# MCU-connectors-schematic.net
KiCad netlist of a schematic drawn in Altium Designer
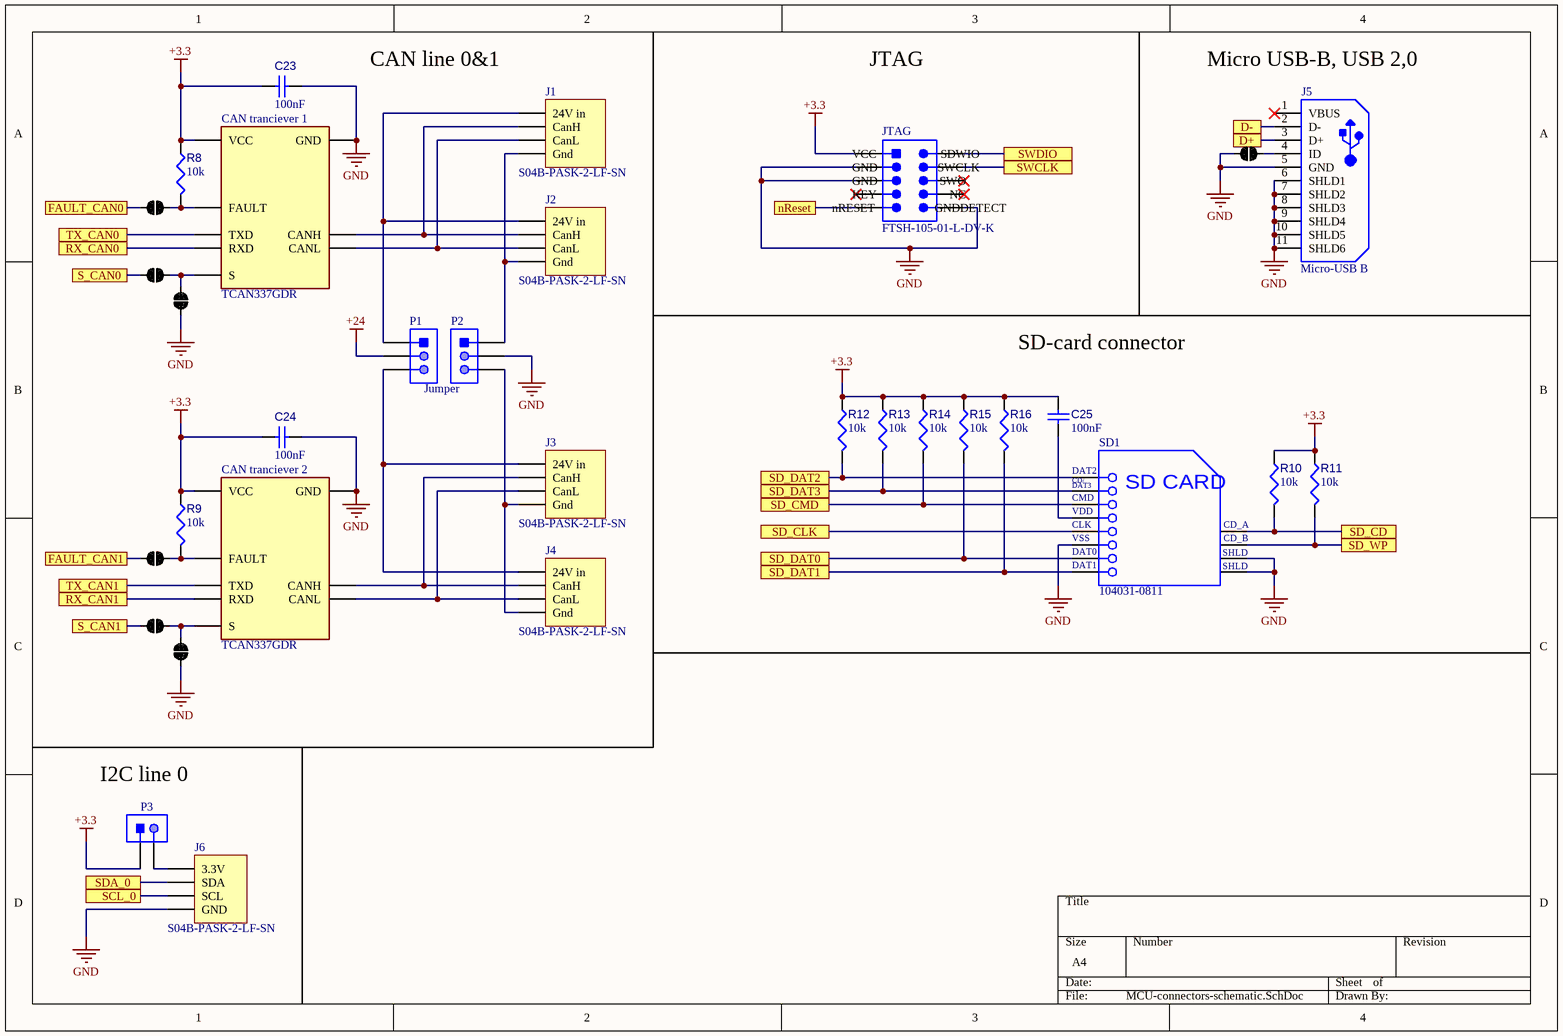
[diagram p0: MCU-connectors-schematic.SchDoc]

(export (version "E")
  (design (tool "Eeschema 10.0.6"))
  (components
    (comp (ref "C23")
      (value "100nF")
      (footprint "CAPC1608X90X40ML10T20")
      (description "Chip Capacitor, 100 nF, +/- 10%, 50 V, 0603 (1608 Metric)")
      (fields (field (name "TOLERANCE") "10%") (field (name "Comment") "Capacitor 100 nF +/-10% 50 V 0603"))
      (libsource (lib "EPFL") (part "CAP-NP-2"))
    )
    (comp (ref "C24")
      (value "100nF")
      (footprint "CAPC1608X90X40ML10T20")
      (description "Chip Capacitor, 100 nF, +/- 10%, 50 V, 0603 (1608 Metric)")
      (fields (field (name "TOLERANCE") "10%") (field (name "Comment") "Capacitor 100 nF +/-10% 50 V 0603"))
      (libsource (lib "EPFL") (part "CAP-NP-2"))
    )
    (comp (ref "C25")
      (value "100nF")
      (footprint "CAPC1608X90X40ML10T20")
      (description "Chip Capacitor, 100 nF, +/- 10%, 50 V, 0603 (1608 Metric)")
      (fields (field (name "TOLERANCE") "10%") (field (name "Comment") "Capacitor 100 nF +/-10% 50 V 0603"))
      (libsource (lib "EPFL") (part "CAP-NP-2"))
    )
    (comp (ref "CAN tranciever 1")
      (value "TCAN337GDR")
      (footprint "FP-D0008A-IPC_B")
      (description "3.3-V CAN Transceivers with CAN FD (Flexible Data Rate) 8-SOIC -40 to 125")
      (libsource (lib "EPFL") (part "a138acb6fe070981c36b7847827baee"))
    )
    (comp (ref "CAN tranciever 2")
      (value "TCAN337GDR")
      (footprint "FP-D0008A-IPC_B")
      (description "3.3-V CAN Transceivers with CAN FD (Flexible Data Rate) 8-SOIC -40 to 125")
      (libsource (lib "EPFL") (part "a138acb6fe070981c36b7847827baee"))
    )
    (comp (ref "J1")
      (value "S04B-PASK-2-LF-SN")
      (footprint "JST-B4B-PH-K-S_V")
      (libsource (lib "EPFL") (part "New symbol 1"))
    )
    (comp (ref "J2")
      (value "S04B-PASK-2-LF-SN")
      (footprint "JST-B4B-PH-K-S_V")
      (libsource (lib "EPFL") (part "New symbol 1"))
    )
    (comp (ref "J3")
      (value "S04B-PASK-2-LF-SN")
      (footprint "JST-B4B-PH-K-S_V")
      (libsource (lib "EPFL") (part "New symbol 1"))
    )
    (comp (ref "J4")
      (value "S04B-PASK-2-LF-SN")
      (footprint "JST-B4B-PH-K-S_V")
      (libsource (lib "EPFL") (part "New symbol 1"))
    )
    (comp (ref "J5")
      (value "Micro-USB B")
      (footprint "USB-MICRO-B_V")
      (fields (field (name "MANUFACTURER") "Molex"))
      (libsource (lib "Altium Content Vault") (part "USB-5-6SHLD"))
    )
    (comp (ref "J6")
      (value "S04B-PASK-2-LF-SN")
      (footprint "JST-B4B-PH-K-S_V")
      (libsource (lib "EPFL") (part "I2C connector"))
    )
    (comp (ref "JTAG")
      (value "FTSH-105-01-L-DV-K")
      (footprint "SMTC-FTSH-105-01-L-DV-K_V")
      (description "Male Header, Pitch 1.27 mm, 2 x 5 Position, Height 6.25 mm")
      (fields (field (name "MANUFACTURER") "Samtec"))
      (libsource (lib "Altium Content Vault") (part "CN-2P-M-R10"))
    )
    (comp (ref "P1")
      (value "22-28-4033")
      (footprint "MOLX-22-28-4033_V")
      (description "Male Header, Pitch 2.54 mm, 1 x 3 Position, Height 8.38 mm, Tail Length 3.18 mm, RoHS, Bulk")
      (fields (field (name "MANUFACTURER") "Molex"))
      (libsource (lib "Altium Content Vault") (part "CN-1P-M-R3"))
    )
    (comp (ref "P2")
      (value "22-28-4033")
      (footprint "MOLX-22-28-4033_V")
      (description "Male Header, Pitch 2.54 mm, 1 x 3 Position, Height 8.38 mm, Tail Length 3.18 mm, RoHS, Bulk")
      (fields (field (name "MANUFACTURER") "Molex"))
      (libsource (lib "") (part "CN-1P-M-R3_1"))
    )
    (comp (ref "P3")
      (value "61900211121")
      (footprint "61900211121")
      (description "Male Locking Header WR-WTB, THT, Vertical, pitch 2.54 mm, 1 x 2 position")
      (fields (field (name "MANUFACTURER") "Wurth Elektronik") (field (name "PUBLISHER") "WurthElektronik"))
      (libsource (lib "Altium Content Vault") (part "WE-CN-1P-M-R2"))
    )
    (comp (ref "R8")
      (value "10k")
      (footprint "RESC1608X55X25ML10T15")
      (description "Chip Resistor, 10 KOhm, +/- 1%, 01 W, -55 to 155 degC, 0603 (1608 Metric)")
      (fields (field (name "TOLERANCE") "1%") (field (name "POWER") "100mW"))
      (libsource (lib "EPFL") (part "RES-2"))
    )
    (comp (ref "R9")
      (value "10k")
      (footprint "RESC1608X55X25ML10T15")
      (description "Chip Resistor, 10 KOhm, +/- 1%, 01 W, -55 to 155 degC, 0603 (1608 Metric)")
      (fields (field (name "TOLERANCE") "1%") (field (name "POWER") "100mW"))
      (libsource (lib "EPFL") (part "RES-2"))
    )
    (comp (ref "R10")
      (value "10k")
      (footprint "RESC1608X55X25ML10T15")
      (description "Chip Resistor, 10 KOhm, +/- 1%, 01 W, -55 to 155 degC, 0603 (1608 Metric)")
      (fields (field (name "TOLERANCE") "1%") (field (name "POWER") "100mW"))
      (libsource (lib "EPFL") (part "RES-2"))
    )
    (comp (ref "R11")
      (value "10k")
      (footprint "RESC1608X55X25ML10T15")
      (description "Chip Resistor, 10 KOhm, +/- 1%, 01 W, -55 to 155 degC, 0603 (1608 Metric)")
      (fields (field (name "TOLERANCE") "1%") (field (name "POWER") "100mW"))
      (libsource (lib "EPFL") (part "RES-2"))
    )
    (comp (ref "R12")
      (value "10k")
      (footprint "RESC1608X55X25ML10T15")
      (description "Chip Resistor, 10 KOhm, +/- 1%, 01 W, -55 to 155 degC, 0603 (1608 Metric)")
      (fields (field (name "TOLERANCE") "1%") (field (name "POWER") "100mW"))
      (libsource (lib "EPFL") (part "RES-2"))
    )
    (comp (ref "R13")
      (value "10k")
      (footprint "RESC1608X55X25ML10T15")
      (description "Chip Resistor, 10 KOhm, +/- 1%, 01 W, -55 to 155 degC, 0603 (1608 Metric)")
      (fields (field (name "TOLERANCE") "1%") (field (name "POWER") "100mW"))
      (libsource (lib "EPFL") (part "RES-2"))
    )
    (comp (ref "R14")
      (value "10k")
      (footprint "RESC1608X55X25ML10T15")
      (description "Chip Resistor, 10 KOhm, +/- 1%, 01 W, -55 to 155 degC, 0603 (1608 Metric)")
      (fields (field (name "TOLERANCE") "1%") (field (name "POWER") "100mW"))
      (libsource (lib "EPFL") (part "RES-2"))
    )
    (comp (ref "R15")
      (value "10k")
      (footprint "RESC1608X55X25ML10T15")
      (description "Chip Resistor, 10 KOhm, +/- 1%, 01 W, -55 to 155 degC, 0603 (1608 Metric)")
      (fields (field (name "TOLERANCE") "1%") (field (name "POWER") "100mW"))
      (libsource (lib "EPFL") (part "RES-2"))
    )
    (comp (ref "R16")
      (value "10k")
      (footprint "RESC1608X55X25ML10T15")
      (description "Chip Resistor, 10 KOhm, +/- 1%, 01 W, -55 to 155 degC, 0603 (1608 Metric)")
      (fields (field (name "TOLERANCE") "1%") (field (name "POWER") "100mW"))
      (libsource (lib "EPFL") (part "RES-2"))
    )
    (comp (ref "SD1")
      (value "104031-0811")
      (footprint "MOLX-104031-0811_V")
      (description "Micro SD Card, RA, -25 to 85 degC, 8-Pin SMD, RoHS, Tape and Reel")
      (fields (field (name "MANUFACTURER") "Molex"))
      (libsource (lib "Altium Content Vault") (part "CN-SD-8-2SW-2S"))
    )
    (comp (ref "SJ1")
      (value "custom Solder bridge")
      (footprint "custom Solder bridge-Footprint-1")
      (description "custom solder bridge")
      (libsource (lib "EPFL") (part "Solder bridge"))
    )
    (comp (ref "SJ2")
      (value "custom Solder bridge")
      (footprint "custom Solder bridge-Footprint-1")
      (description "custom solder bridge")
      (libsource (lib "EPFL") (part "Solder bridge"))
    )
    (comp (ref "SJ3")
      (value "custom Solder bridge")
      (footprint "custom Solder bridge-Footprint-1")
      (description "custom solder bridge")
      (libsource (lib "EPFL") (part "Solder bridge"))
    )
    (comp (ref "SJ4")
      (value "custom Solder bridge")
      (footprint "custom Solder bridge-Footprint-1")
      (description "custom solder bridge")
      (libsource (lib "EPFL") (part "Solder bridge"))
    )
    (comp (ref "SJ5")
      (value "custom Solder bridge")
      (footprint "custom Solder bridge-Footprint-1")
      (description "custom solder bridge")
      (libsource (lib "EPFL") (part "Solder bridge"))
    )
    (comp (ref "SJ6")
      (value "custom Solder bridge")
      (footprint "custom Solder bridge-Footprint-1")
      (description "custom solder bridge")
      (libsource (lib "EPFL") (part "Solder bridge"))
    )
    (comp (ref "SJ7")
      (value "custom Solder bridge")
      (footprint "custom Solder bridge-Footprint-1")
      (description "custom solder bridge")
      (libsource (lib "EPFL") (part "Solder bridge"))
    )
  )
  (nets
    (net (code "1") (name "+3.3") (class "Default")
      (node (ref "C23") (pin "2") (pinfunction "2_2") (pintype "passive"))
      (node (ref "C24") (pin "2") (pinfunction "2_2") (pintype "passive"))
      (node (ref "C25") (pin "2") (pinfunction "2_2") (pintype "passive"))
      (node (ref "CAN tranciever 1") (pin "3") (pinfunction "VCC_3") (pintype "power_in"))
      (node (ref "CAN tranciever 2") (pin "3") (pinfunction "VCC_3") (pintype "power_in"))
      (node (ref "JTAG") (pin "1") (pinfunction "VCC_1") (pintype "passive"))
      (node (ref "P3") (pin "1") (pinfunction "1_1") (pintype "passive"))
      (node (ref "R10") (pin "1") (pinfunction "1_1") (pintype "passive"))
      (node (ref "R11") (pin "1") (pinfunction "1_1") (pintype "passive"))
      (node (ref "R12") (pin "1") (pinfunction "1_1") (pintype "passive"))
      (node (ref "R13") (pin "1") (pinfunction "1_1") (pintype "passive"))
      (node (ref "R14") (pin "1") (pinfunction "1_1") (pintype "passive"))
      (node (ref "R15") (pin "1") (pinfunction "1_1") (pintype "passive"))
      (node (ref "R16") (pin "1") (pinfunction "1_1") (pintype "passive"))
      (node (ref "R8") (pin "1") (pinfunction "1_1") (pintype "passive"))
      (node (ref "R9") (pin "1") (pinfunction "1_1") (pintype "passive"))
    )
    (net (code "2") (name "+24") (class "Default")
      (node (ref "P1") (pin "2") (pinfunction "2_2") (pintype "passive"))
    )
    (net (code "3") (name "/D+") (class "Default")
      (node (ref "J5") (pin "3") (pinfunction "D+_3") (pintype "passive"))
    )
    (net (code "4") (name "/D-") (class "Default")
      (node (ref "J5") (pin "2") (pinfunction "D-_2") (pintype "passive"))
    )
    (net (code "5") (name "/FAULT_CAN0") (class "Default")
      (node (ref "SJ6") (pin "1") (pinfunction "1_1") (pintype "passive"))
    )
    (net (code "6") (name "/FAULT_CAN1") (class "Default")
      (node (ref "SJ3") (pin "1") (pinfunction "1_1") (pintype "passive"))
    )
    (net (code "7") (name "/RX_CAN0") (class "Default")
      (node (ref "CAN tranciever 1") (pin "4") (pinfunction "RXD_4") (pintype "passive"))
    )
    (net (code "8") (name "/RX_CAN1") (class "Default")
      (node (ref "CAN tranciever 2") (pin "4") (pinfunction "RXD_4") (pintype "passive"))
    )
    (net (code "9") (name "/SCL_0") (class "Default")
      (node (ref "J6") (pin "3") (pinfunction "SCL_3") (pintype "passive"))
    )
    (net (code "10") (name "/SDA_0") (class "Default")
      (node (ref "J6") (pin "2") (pinfunction "SDA_2") (pintype "passive"))
    )
    (net (code "11") (name "/SD_CD") (class "Default")
      (node (ref "R10") (pin "2") (pinfunction "2_2") (pintype "passive"))
      (node (ref "SD1") (pin "9") (pinfunction "CD_A_9") (pintype "passive"))
    )
    (net (code "12") (name "/SD_CLK") (class "Default")
      (node (ref "SD1") (pin "5") (pinfunction "CLK_5") (pintype "passive"))
    )
    (net (code "13") (name "/SD_CMD") (class "Default")
      (node (ref "R14") (pin "2") (pinfunction "2_2") (pintype "passive"))
      (node (ref "SD1") (pin "3") (pinfunction "VSS1_3") (pintype "passive"))
    )
    (net (code "14") (name "/SD_DAT0") (class "Default")
      (node (ref "R15") (pin "2") (pinfunction "2_2") (pintype "passive"))
      (node (ref "SD1") (pin "7") (pinfunction "DAT0_7") (pintype "passive"))
    )
    (net (code "15") (name "/SD_DAT1") (class "Default")
      (node (ref "R16") (pin "2") (pinfunction "2_2") (pintype "passive"))
      (node (ref "SD1") (pin "8") (pinfunction "DAT1_8") (pintype "passive"))
    )
    (net (code "16") (name "/SD_DAT2") (class "Default")
      (node (ref "R12") (pin "2") (pinfunction "2_2") (pintype "passive"))
      (node (ref "SD1") (pin "1") (pinfunction "CD/DAT3_1") (pintype "passive"))
    )
    (net (code "17") (name "/SD_DAT3") (class "Default")
      (node (ref "R13") (pin "2") (pinfunction "2_2") (pintype "passive"))
      (node (ref "SD1") (pin "2") (pinfunction "CMD_2") (pintype "passive"))
    )
    (net (code "18") (name "/SD_WP") (class "Default")
      (node (ref "R11") (pin "2") (pinfunction "2_2") (pintype "passive"))
      (node (ref "SD1") (pin "10") (pinfunction "CD_B_10") (pintype "passive"))
    )
    (net (code "19") (name "/SWCLK") (class "Default")
      (node (ref "JTAG") (pin "4") (pinfunction "SWCLK_4") (pintype "passive"))
    )
    (net (code "20") (name "/SWDIO") (class "Default")
      (node (ref "JTAG") (pin "2") (pinfunction "SDWIO_2") (pintype "passive"))
    )
    (net (code "21") (name "/S_CAN0") (class "Default")
      (node (ref "SJ5") (pin "1") (pinfunction "1_1") (pintype "passive"))
    )
    (net (code "22") (name "/S_CAN1") (class "Default")
      (node (ref "SJ2") (pin "1") (pinfunction "1_1") (pintype "passive"))
    )
    (net (code "23") (name "/TX_CAN0") (class "Default")
      (node (ref "CAN tranciever 1") (pin "1") (pinfunction "TXD_1") (pintype "passive"))
    )
    (net (code "24") (name "/TX_CAN1") (class "Default")
      (node (ref "CAN tranciever 2") (pin "1") (pinfunction "TXD_1") (pintype "passive"))
    )
    (net (code "25") (name "/nReset") (class "Default")
      (node (ref "JTAG") (pin "9") (pinfunction "nRESET_9") (pintype "passive"))
    )
    (net (code "26") (name "GND") (class "Default")
      (node (ref "C23") (pin "1") (pinfunction "1_1") (pintype "passive"))
      (node (ref "C24") (pin "1") (pinfunction "1_1") (pintype "passive"))
      (node (ref "CAN tranciever 1") (pin "2") (pinfunction "GND_2") (pintype "power_in"))
      (node (ref "CAN tranciever 2") (pin "2") (pinfunction "GND_2") (pintype "power_in"))
      (node (ref "J5") (pin "10") (pinfunction "SHLD5_10") (pintype "passive"))
      (node (ref "J5") (pin "11") (pinfunction "SHLD6_11") (pintype "passive"))
      (node (ref "J5") (pin "5") (pinfunction "GND_5") (pintype "passive"))
      (node (ref "J5") (pin "6") (pinfunction "SHLD1_6") (pintype "passive"))
      (node (ref "J5") (pin "7") (pinfunction "SHLD2_7") (pintype "passive"))
      (node (ref "J5") (pin "8") (pinfunction "SHLD3_8") (pintype "passive"))
      (node (ref "J5") (pin "9") (pinfunction "SHLD4_9") (pintype "passive"))
      (node (ref "J6") (pin "4") (pinfunction "GND_4") (pintype "power_in"))
      (node (ref "JTAG") (pin "10") (pinfunction "GNDDETECT_10") (pintype "passive"))
      (node (ref "JTAG") (pin "3") (pinfunction "GND_3") (pintype "passive"))
      (node (ref "JTAG") (pin "5") (pinfunction "GND_5") (pintype "passive"))
      (node (ref "P2") (pin "2") (pinfunction "2_2") (pintype "passive"))
      (node (ref "SD1") (pin "11") (pinfunction "SHLD1_11") (pintype "passive"))
      (node (ref "SD1") (pin "12") (pinfunction "SHLD2_12") (pintype "passive"))
      (node (ref "SD1") (pin "6") (pinfunction "VSS2_6") (pintype "passive"))
      (node (ref "SJ1") (pin "1") (pinfunction "1_1") (pintype "passive"))
      (node (ref "SJ4") (pin "1") (pinfunction "1_1") (pintype "passive"))
      (node (ref "SJ7") (pin "1") (pinfunction "1_1") (pintype "passive"))
    )
    (net (code "27") (name "Net-(CAN tranciever 1-CANH)") (class "Default")
      (node (ref "CAN tranciever 1") (pin "7") (pinfunction "CANH_7") (pintype "passive"))
      (node (ref "J1") (pin "2") (pinfunction "CanH_2") (pintype "passive"))
      (node (ref "J2") (pin "2") (pinfunction "CanH_2") (pintype "passive"))
    )
    (net (code "28") (name "Net-(CAN tranciever 1-CANL)") (class "Default")
      (node (ref "CAN tranciever 1") (pin "6") (pinfunction "CANL_6") (pintype "passive"))
      (node (ref "J1") (pin "3") (pinfunction "CanL_3") (pintype "passive"))
      (node (ref "J2") (pin "3") (pinfunction "CanL_3") (pintype "passive"))
    )
    (net (code "29") (name "Net-(CAN tranciever 1-FAULT)") (class "Default")
      (node (ref "CAN tranciever 1") (pin "5") (pinfunction "FAULT_5") (pintype "passive"))
      (node (ref "R8") (pin "2") (pinfunction "2_2") (pintype "passive"))
      (node (ref "SJ6") (pin "2") (pinfunction "2_2") (pintype "passive"))
    )
    (net (code "30") (name "Net-(CAN tranciever 1-S)") (class "Default")
      (node (ref "CAN tranciever 1") (pin "8") (pinfunction "S_8") (pintype "passive"))
      (node (ref "SJ4") (pin "2") (pinfunction "2_2") (pintype "passive"))
      (node (ref "SJ5") (pin "2") (pinfunction "2_2") (pintype "passive"))
    )
    (net (code "31") (name "Net-(CAN tranciever 2-CANH)") (class "Default")
      (node (ref "CAN tranciever 2") (pin "7") (pinfunction "CANH_7") (pintype "passive"))
      (node (ref "J3") (pin "2") (pinfunction "CanH_2") (pintype "passive"))
      (node (ref "J4") (pin "2") (pinfunction "CanH_2") (pintype "passive"))
    )
    (net (code "32") (name "Net-(CAN tranciever 2-CANL)") (class "Default")
      (node (ref "CAN tranciever 2") (pin "6") (pinfunction "CANL_6") (pintype "passive"))
      (node (ref "J3") (pin "3") (pinfunction "CanL_3") (pintype "passive"))
      (node (ref "J4") (pin "3") (pinfunction "CanL_3") (pintype "passive"))
    )
    (net (code "33") (name "Net-(CAN tranciever 2-FAULT)") (class "Default")
      (node (ref "CAN tranciever 2") (pin "5") (pinfunction "FAULT_5") (pintype "passive"))
      (node (ref "R9") (pin "2") (pinfunction "2_2") (pintype "passive"))
      (node (ref "SJ3") (pin "2") (pinfunction "2_2") (pintype "passive"))
    )
    (net (code "34") (name "Net-(CAN tranciever 2-S)") (class "Default")
      (node (ref "CAN tranciever 2") (pin "8") (pinfunction "S_8") (pintype "passive"))
      (node (ref "SJ1") (pin "2") (pinfunction "2_2") (pintype "passive"))
      (node (ref "SJ2") (pin "2") (pinfunction "2_2") (pintype "passive"))
    )
    (net (code "35") (name "Net-(J1-24V_in)") (class "Default")
      (node (ref "J1") (pin "1") (pinfunction "24V_in_1") (pintype "power_in"))
      (node (ref "J2") (pin "1") (pinfunction "24V_in_1") (pintype "power_in"))
      (node (ref "P1") (pin "1") (pinfunction "1_1") (pintype "passive"))
    )
    (net (code "36") (name "Net-(J1-Gnd)") (class "Default")
      (node (ref "J1") (pin "4") (pinfunction "Gnd_4") (pintype "power_in"))
      (node (ref "J2") (pin "4") (pinfunction "Gnd_4") (pintype "power_in"))
      (node (ref "P2") (pin "1") (pinfunction "1_1") (pintype "passive"))
    )
    (net (code "37") (name "Net-(J3-24V_in)") (class "Default")
      (node (ref "J3") (pin "1") (pinfunction "24V_in_1") (pintype "power_in"))
      (node (ref "J4") (pin "1") (pinfunction "24V_in_1") (pintype "power_in"))
      (node (ref "P1") (pin "3") (pinfunction "3_3") (pintype "passive"))
    )
    (net (code "38") (name "Net-(J3-Gnd)") (class "Default")
      (node (ref "J3") (pin "4") (pinfunction "Gnd_4") (pintype "power_in"))
      (node (ref "J4") (pin "4") (pinfunction "Gnd_4") (pintype "power_in"))
      (node (ref "P2") (pin "3") (pinfunction "3_3") (pintype "passive"))
    )
    (net (code "39") (name "Net-(J5-ID)") (class "Default")
      (node (ref "J5") (pin "4") (pinfunction "ID_4") (pintype "passive"))
      (node (ref "SJ7") (pin "2") (pinfunction "2_2") (pintype "passive"))
    )
    (net (code "40") (name "Net-(J6-3.3V)") (class "Default")
      (node (ref "J6") (pin "1") (pinfunction "3.3V_1") (pintype "power_in"))
      (node (ref "P3") (pin "2") (pinfunction "2_2") (pintype "passive"))
    )
    (net (code "41") (name "Net-(SD1-VDD)") (class "Default")
      (node (ref "C25") (pin "1") (pinfunction "1_1") (pintype "passive"))
      (node (ref "SD1") (pin "4") (pinfunction "VDD_4") (pintype "passive"))
    )
    (net (code "42") (name "unconnected-(J5-VBUS-Pad1)") (class "Default")
      (node (ref "J5") (pin "1") (pinfunction "VBUS_1") (pintype "passive+no_connect"))
    )
    (net (code "43") (name "unconnected-(JTAG-KEY-Pad7)") (class "Default")
      (node (ref "JTAG") (pin "7") (pinfunction "KEY_7") (pintype "passive+no_connect"))
    )
    (net (code "44") (name "unconnected-(JTAG-NC-Pad8)") (class "Default")
      (node (ref "JTAG") (pin "8") (pinfunction "NC_8") (pintype "passive+no_connect"))
    )
    (net (code "45") (name "unconnected-(JTAG-SWO-Pad6)") (class "Default")
      (node (ref "JTAG") (pin "6") (pinfunction "SWO_6") (pintype "passive+no_connect"))
    )
  )
)
